# gate-detector.net
KiCad netlist of a schematic drawn in EAGLE
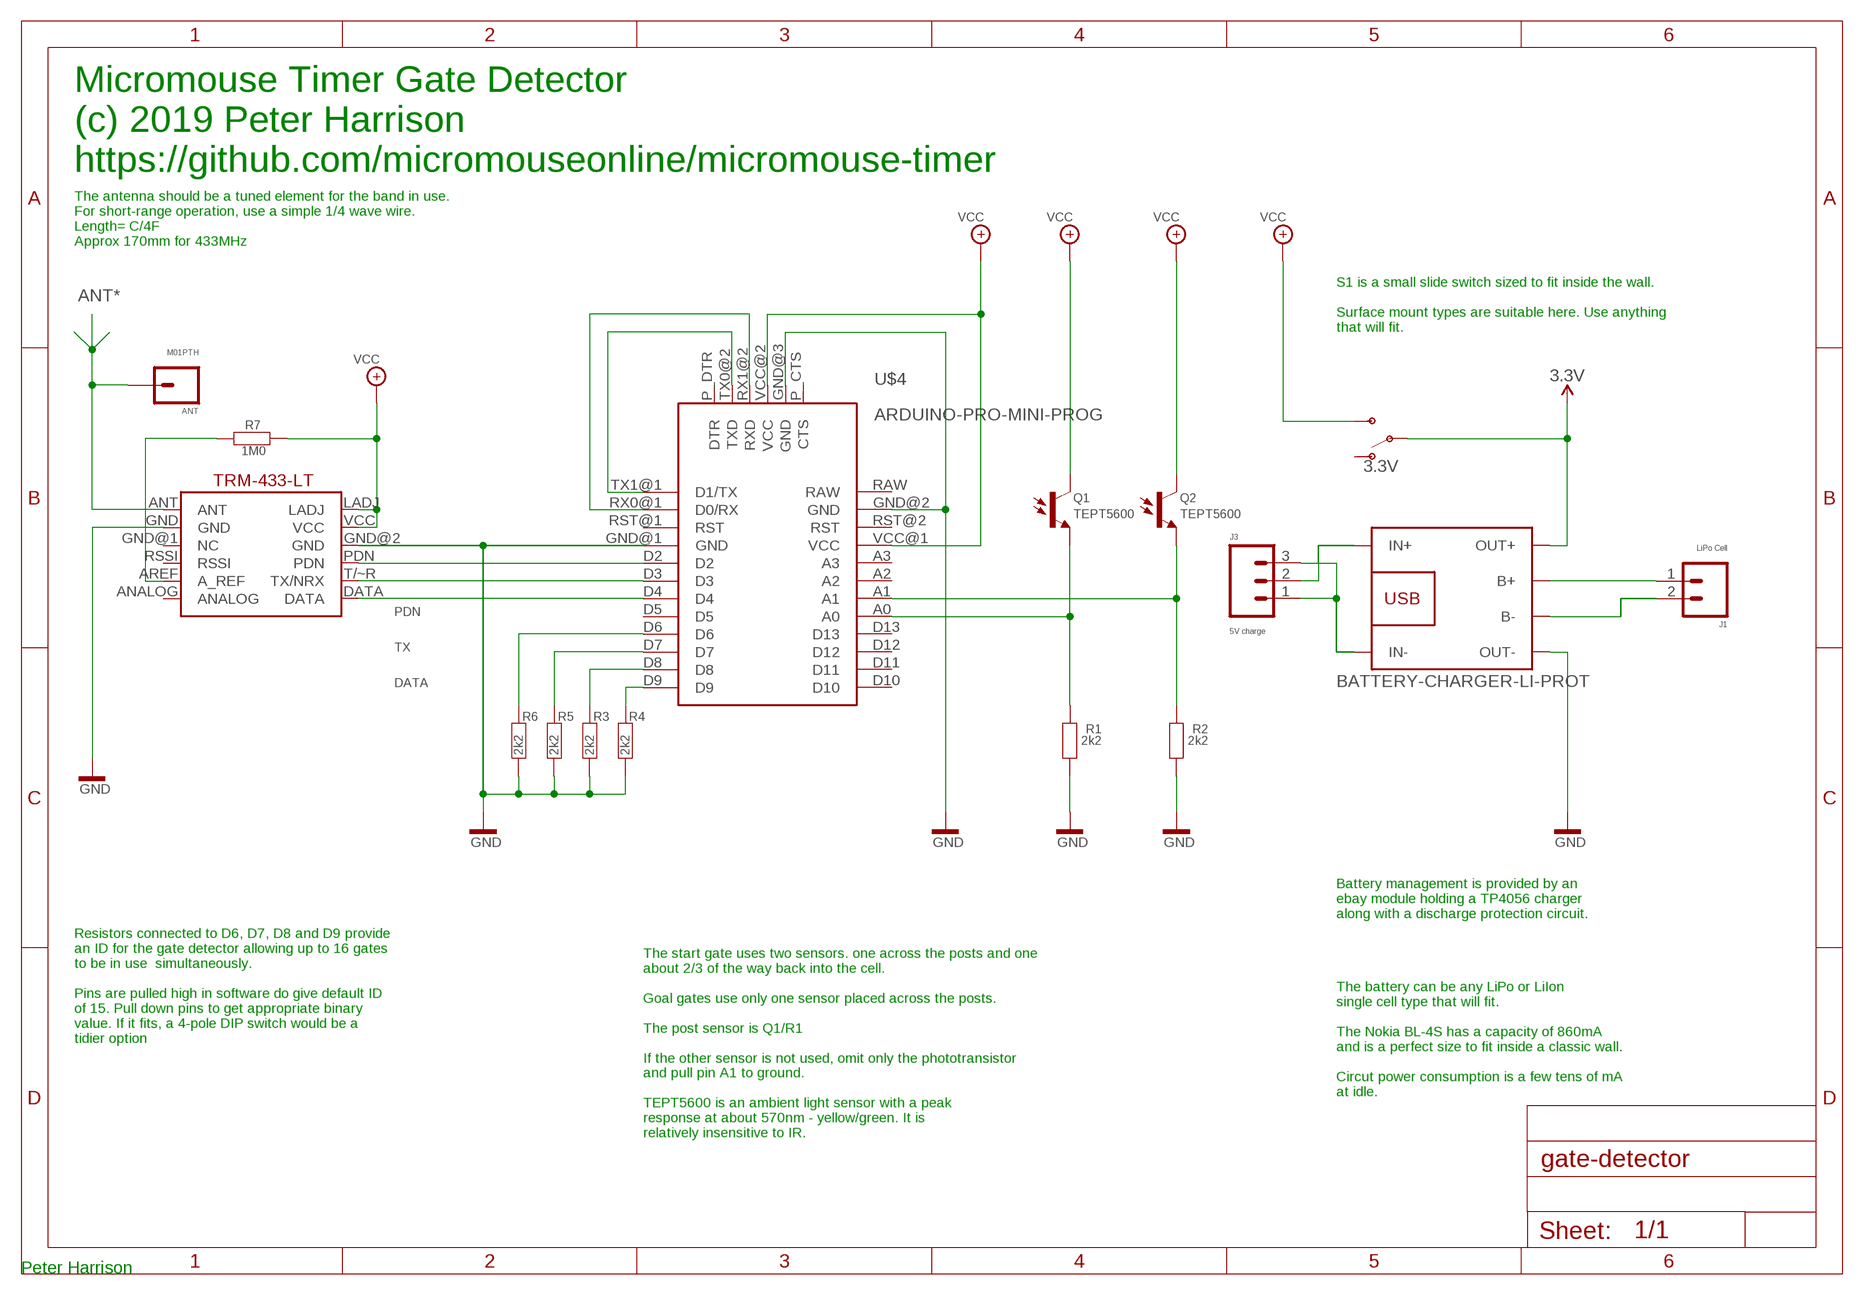
[diagram p0: schematic, sheet 1]

(export (version "E")
  (design (tool "Eeschema 10.0.6"))
  (components
    (comp (ref "3.3V")
      (value "SWITCH-SPDT-PTH-11.6X4.0MM-KIT")
      (footprint "eagle-import:SWITCH_SPDT_PTH_11.6X4.0MM_KIT")
      (libsource (lib "eagle-import") (part "SWITCH-SPDT-PTH-11.6X4.0MM-KIT"))
    )
    (comp (ref "ANT")
      (value "M01PTH")
      (footprint "eagle-import:1X01")
      (libsource (lib "eagle-import") (part "M01PTH"))
    )
    (comp (ref "J1")
      (value "LiPo Cell")
      (footprint "eagle-import:1X02_RA_PTH_MALE_MILL")
      (libsource (lib "eagle-import") (part "M02RA_MALE_MILL"))
    )
    (comp (ref "J3")
      (value "5V charge")
      (footprint "eagle-import:1X03_RA_PTH_MILL")
      (libsource (lib "eagle-import") (part "M03RA_MALE"))
    )
    (comp (ref "Q1")
      (value "TEPT5600")
      (footprint "eagle-import:PHOTOTRANSISTOR-TO5-SIDE")
      (libsource (lib "eagle-import") (part "PHOTO-NPN"))
    )
    (comp (ref "Q2")
      (value "TEPT5600")
      (footprint "eagle-import:PHOTOTRANSISTOR-TO5-SIDE")
      (libsource (lib "eagle-import") (part "PHOTO-NPN"))
    )
    (comp (ref "R1")
      (value "2k2")
      (footprint "eagle-import:AXIAL-0207_0.4")
      (libsource (lib "eagle-import") (part "RESISTOR_AXIAL-0207_0.4"))
    )
    (comp (ref "R2")
      (value "2k2")
      (footprint "eagle-import:AXIAL-0207_0.4")
      (libsource (lib "eagle-import") (part "RESISTOR_AXIAL-0207_0.4"))
    )
    (comp (ref "R3")
      (value "2k2")
      (footprint "eagle-import:AXIAL-0207_0.4")
      (libsource (lib "eagle-import") (part "RESISTOR_AXIAL-0207_0.4"))
    )
    (comp (ref "R4")
      (value "2k2")
      (footprint "eagle-import:AXIAL-0207_0.4")
      (libsource (lib "eagle-import") (part "RESISTOR_AXIAL-0207_0.4"))
    )
    (comp (ref "R5")
      (value "2k2")
      (footprint "eagle-import:AXIAL-0207_0.4")
      (libsource (lib "eagle-import") (part "RESISTOR_AXIAL-0207_0.4"))
    )
    (comp (ref "R6")
      (value "2k2")
      (footprint "eagle-import:AXIAL-0207_0.4")
      (libsource (lib "eagle-import") (part "RESISTOR_AXIAL-0207_0.4"))
    )
    (comp (ref "R7")
      (value "1M0")
      (footprint "eagle-import:AXIAL-0207_0.4")
      (libsource (lib "eagle-import") (part "RESISTOR_AXIAL-0207_0.4"))
    )
    (comp (ref "U$1")
      (value "TRM-433-LT")
      (footprint "eagle-import:LINX-TRM-433-LT")
      (libsource (lib "eagle-import") (part "TRM-433-LT"))
    )
    (comp (ref "U$2")
      (value "BATTERY-CHARGER-LI-PROT")
      (footprint "eagle-import:BATTERY-CHARGER-LI-PROT")
      (libsource (lib "eagle-import") (part "BATTERY-CHARGER-LI-PROT"))
    )
    (comp (ref "U$4")
      (value "ARDUINO-PRO-MINI-PROG")
      (footprint "eagle-import:ARDUINO-PRO-MINI-PROG")
      (libsource (lib "eagle-import") (part "ARDUINO-PRO-MINI-PROG"))
    )
  )
  (nets
    (net (code "1") (name "/ANT*") (class "Default")
      (node (ref "ANT") (pin "1") (pinfunction "1_1") (pintype "passive"))
      (node (ref "U$1") (pin "ANT") (pinfunction "ANT_ANT") (pintype "passive"))
    )
    (net (code "2") (name "/DATA") (class "Default")
      (node (ref "U$1") (pin "DATA") (pinfunction "DATA_DATA") (pintype "bidirectional"))
      (node (ref "U$4") (pin "D4") (pinfunction "D4_D4") (pintype "bidirectional"))
    )
    (net (code "3") (name "/PDN") (class "Default")
      (node (ref "U$1") (pin "PDN") (pinfunction "PDN_PDN") (pintype "input"))
      (node (ref "U$4") (pin "D2") (pinfunction "D2_D2") (pintype "bidirectional"))
    )
    (net (code "4") (name "/RAW") (class "Default")
      (node (ref "U$4") (pin "RAW") (pinfunction "RAW_RAW") (pintype "power_in"))
    )
    (net (code "5") (name "/TX") (class "Default")
      (node (ref "U$1") (pin "T/~R") (pinfunction "TX/NRX_T/~R") (pintype "input"))
      (node (ref "U$4") (pin "D3") (pinfunction "D3_D3") (pintype "bidirectional"))
    )
    (net (code "6") (name "3.3V") (class "Default")
      (node (ref "3.3V") (pin "2") (pinfunction "P_2") (pintype "passive"))
      (node (ref "U$2") (pin "OUT+") (pinfunction "OUT+_OUT+") (pintype "bidirectional"))
    )
    (net (code "7") (name "GND") (class "Default")
      (node (ref "R1") (pin "1") (pinfunction "1_1") (pintype "passive"))
      (node (ref "R2") (pin "1") (pinfunction "1_1") (pintype "passive"))
      (node (ref "R3") (pin "1") (pinfunction "1_1") (pintype "passive"))
      (node (ref "R4") (pin "1") (pinfunction "1_1") (pintype "passive"))
      (node (ref "R5") (pin "1") (pinfunction "1_1") (pintype "passive"))
      (node (ref "R6") (pin "1") (pinfunction "1_1") (pintype "passive"))
      (node (ref "U$1") (pin "GND") (pinfunction "GND_GND") (pintype "power_in"))
      (node (ref "U$1") (pin "GND@2") (pinfunction "GND_GND@2") (pintype "power_in"))
      (node (ref "U$2") (pin "OUT-") (pinfunction "OUT-_OUT-") (pintype "bidirectional"))
      (node (ref "U$4") (pin "GND@1") (pinfunction "GND_GND@1") (pintype "power_in"))
      (node (ref "U$4") (pin "GND@2") (pinfunction "GND_GND@2") (pintype "power_in"))
      (node (ref "U$4") (pin "GND@3") (pinfunction "GND_GND@3") (pintype "bidirectional"))
    )
    (net (code "8") (name "Net-(J1-Pad1)") (class "Default")
      (node (ref "J1") (pin "1") (pinfunction "1_1") (pintype "passive"))
      (node (ref "U$2") (pin "B+") (pinfunction "B+_B+") (pintype "bidirectional"))
    )
    (net (code "9") (name "Net-(J1-Pad2)") (class "Default")
      (node (ref "J1") (pin "2") (pinfunction "2_2") (pintype "passive"))
      (node (ref "U$2") (pin "B-") (pinfunction "B-_B-") (pintype "bidirectional"))
    )
    (net (code "10") (name "Net-(J3-Pad1)") (class "Default")
      (node (ref "J3") (pin "1") (pinfunction "1_1") (pintype "passive"))
      (node (ref "J3") (pin "3") (pinfunction "3_3") (pintype "passive"))
      (node (ref "U$2") (pin "IN-") (pinfunction "IN-_IN-") (pintype "bidirectional"))
    )
    (net (code "11") (name "Net-(J3-Pad2)") (class "Default")
      (node (ref "J3") (pin "2") (pinfunction "2_2") (pintype "passive"))
      (node (ref "U$2") (pin "IN+") (pinfunction "IN+_IN+") (pintype "bidirectional"))
    )
    (net (code "12") (name "Net-(Q1-PadE)") (class "Default")
      (node (ref "Q1") (pin "E") (pinfunction "E_E") (pintype "passive"))
      (node (ref "R1") (pin "2") (pinfunction "2_2") (pintype "passive"))
      (node (ref "U$4") (pin "A0") (pinfunction "A0_A0") (pintype "bidirectional"))
    )
    (net (code "13") (name "Net-(Q2-PadE)") (class "Default")
      (node (ref "Q2") (pin "E") (pinfunction "E_E") (pintype "passive"))
      (node (ref "R2") (pin "2") (pinfunction "2_2") (pintype "passive"))
      (node (ref "U$4") (pin "A1") (pinfunction "A1_A1") (pintype "bidirectional"))
    )
    (net (code "14") (name "Net-(R3-Pad2)") (class "Default")
      (node (ref "R3") (pin "2") (pinfunction "2_2") (pintype "passive"))
      (node (ref "U$4") (pin "D8") (pinfunction "D8_D8") (pintype "bidirectional"))
    )
    (net (code "15") (name "Net-(R4-Pad2)") (class "Default")
      (node (ref "R4") (pin "2") (pinfunction "2_2") (pintype "passive"))
      (node (ref "U$4") (pin "D9") (pinfunction "D9_D9") (pintype "bidirectional"))
    )
    (net (code "16") (name "Net-(R5-Pad2)") (class "Default")
      (node (ref "R5") (pin "2") (pinfunction "2_2") (pintype "passive"))
      (node (ref "U$4") (pin "D7") (pinfunction "D7_D7") (pintype "bidirectional"))
    )
    (net (code "17") (name "Net-(R6-Pad2)") (class "Default")
      (node (ref "R6") (pin "2") (pinfunction "2_2") (pintype "passive"))
      (node (ref "U$4") (pin "D6") (pinfunction "D6_D6") (pintype "bidirectional"))
    )
    (net (code "18") (name "Net-(U$1-A_REF)") (class "Default")
      (node (ref "R7") (pin "2") (pinfunction "2_2") (pintype "passive"))
      (node (ref "U$1") (pin "AREF") (pinfunction "A_REF_AREF") (pintype "bidirectional"))
    )
    (net (code "19") (name "Net-(U$4-D0{slash}RX)") (class "Default")
      (node (ref "U$4") (pin "RX0@1") (pinfunction "D0/RX_RX0@1") (pintype "bidirectional"))
      (node (ref "U$4") (pin "RX1@2") (pinfunction "RXD_RX1@2") (pintype "bidirectional"))
    )
    (net (code "20") (name "Net-(U$4-D1{slash}TX)") (class "Default")
      (node (ref "U$4") (pin "TX0@2") (pinfunction "TXD_TX0@2") (pintype "bidirectional"))
      (node (ref "U$4") (pin "TX1@1") (pinfunction "D1/TX_TX1@1") (pintype "bidirectional"))
    )
    (net (code "21") (name "VCC") (class "Default")
      (node (ref "3.3V") (pin "3") (pinfunction "S_3") (pintype "passive"))
      (node (ref "Q1") (pin "C") (pinfunction "C_C") (pintype "passive"))
      (node (ref "Q2") (pin "C") (pinfunction "C_C") (pintype "passive"))
      (node (ref "R7") (pin "1") (pinfunction "1_1") (pintype "passive"))
      (node (ref "U$1") (pin "LADJ") (pinfunction "LADJ_LADJ") (pintype "bidirectional"))
      (node (ref "U$1") (pin "VCC") (pinfunction "VCC_VCC") (pintype "power_in"))
      (node (ref "U$4") (pin "VCC@1") (pinfunction "VCC_VCC@1") (pintype "power_in"))
      (node (ref "U$4") (pin "VCC@2") (pinfunction "VCC_VCC@2") (pintype "bidirectional"))
    )
    (net (code "22") (name "unconnected-(3.3V-O-Pad1)") (class "Default")
      (node (ref "3.3V") (pin "1") (pinfunction "O_1") (pintype "passive"))
    )
    (net (code "23") (name "unconnected-(U$1-NC-PadGND@1)") (class "Default")
      (node (ref "U$1") (pin "GND@1") (pinfunction "NC_GND@1") (pintype "no_connect"))
    )
    (net (code "24") (name "unconnected-(U$1-PadANALOG)") (class "Default")
      (node (ref "U$1") (pin "ANALOG") (pinfunction "ANALOG_ANALOG") (pintype "bidirectional"))
    )
    (net (code "25") (name "unconnected-(U$1-PadRSSI)") (class "Default")
      (node (ref "U$1") (pin "RSSI") (pinfunction "RSSI_RSSI") (pintype "output"))
    )
    (net (code "26") (name "unconnected-(U$4-CTS-PadP_CTS)") (class "Default")
      (node (ref "U$4") (pin "P_CTS") (pinfunction "CTS_P_CTS") (pintype "bidirectional"))
    )
    (net (code "27") (name "unconnected-(U$4-DTR-PadP_DTR)") (class "Default")
      (node (ref "U$4") (pin "P_DTR") (pinfunction "DTR_P_DTR") (pintype "bidirectional"))
    )
    (net (code "28") (name "unconnected-(U$4-PadA2)") (class "Default")
      (node (ref "U$4") (pin "A2") (pinfunction "A2_A2") (pintype "bidirectional"))
    )
    (net (code "29") (name "unconnected-(U$4-PadA3)") (class "Default")
      (node (ref "U$4") (pin "A3") (pinfunction "A3_A3") (pintype "bidirectional"))
    )
    (net (code "30") (name "unconnected-(U$4-PadD5)") (class "Default")
      (node (ref "U$4") (pin "D5") (pinfunction "D5_D5") (pintype "bidirectional"))
    )
    (net (code "31") (name "unconnected-(U$4-PadD10)") (class "Default")
      (node (ref "U$4") (pin "D10") (pinfunction "D10_D10") (pintype "bidirectional"))
    )
    (net (code "32") (name "unconnected-(U$4-PadD11)") (class "Default")
      (node (ref "U$4") (pin "D11") (pinfunction "D11_D11") (pintype "bidirectional"))
    )
    (net (code "33") (name "unconnected-(U$4-PadD12)") (class "Default")
      (node (ref "U$4") (pin "D12") (pinfunction "D12_D12") (pintype "bidirectional"))
    )
    (net (code "34") (name "unconnected-(U$4-PadD13)") (class "Default")
      (node (ref "U$4") (pin "D13") (pinfunction "D13_D13") (pintype "bidirectional"))
    )
    (net (code "35") (name "unconnected-(U$4-RST-PadRST@1)") (class "Default")
      (node (ref "U$4") (pin "RST@1") (pinfunction "RST_RST@1") (pintype "bidirectional"))
    )
    (net (code "36") (name "unconnected-(U$4-RST-PadRST@2)") (class "Default")
      (node (ref "U$4") (pin "RST@2") (pinfunction "RST_RST@2") (pintype "bidirectional"))
    )
  )
)
